# Sensors_1.net
KiCad netlist of a schematic drawn in Altium Designer
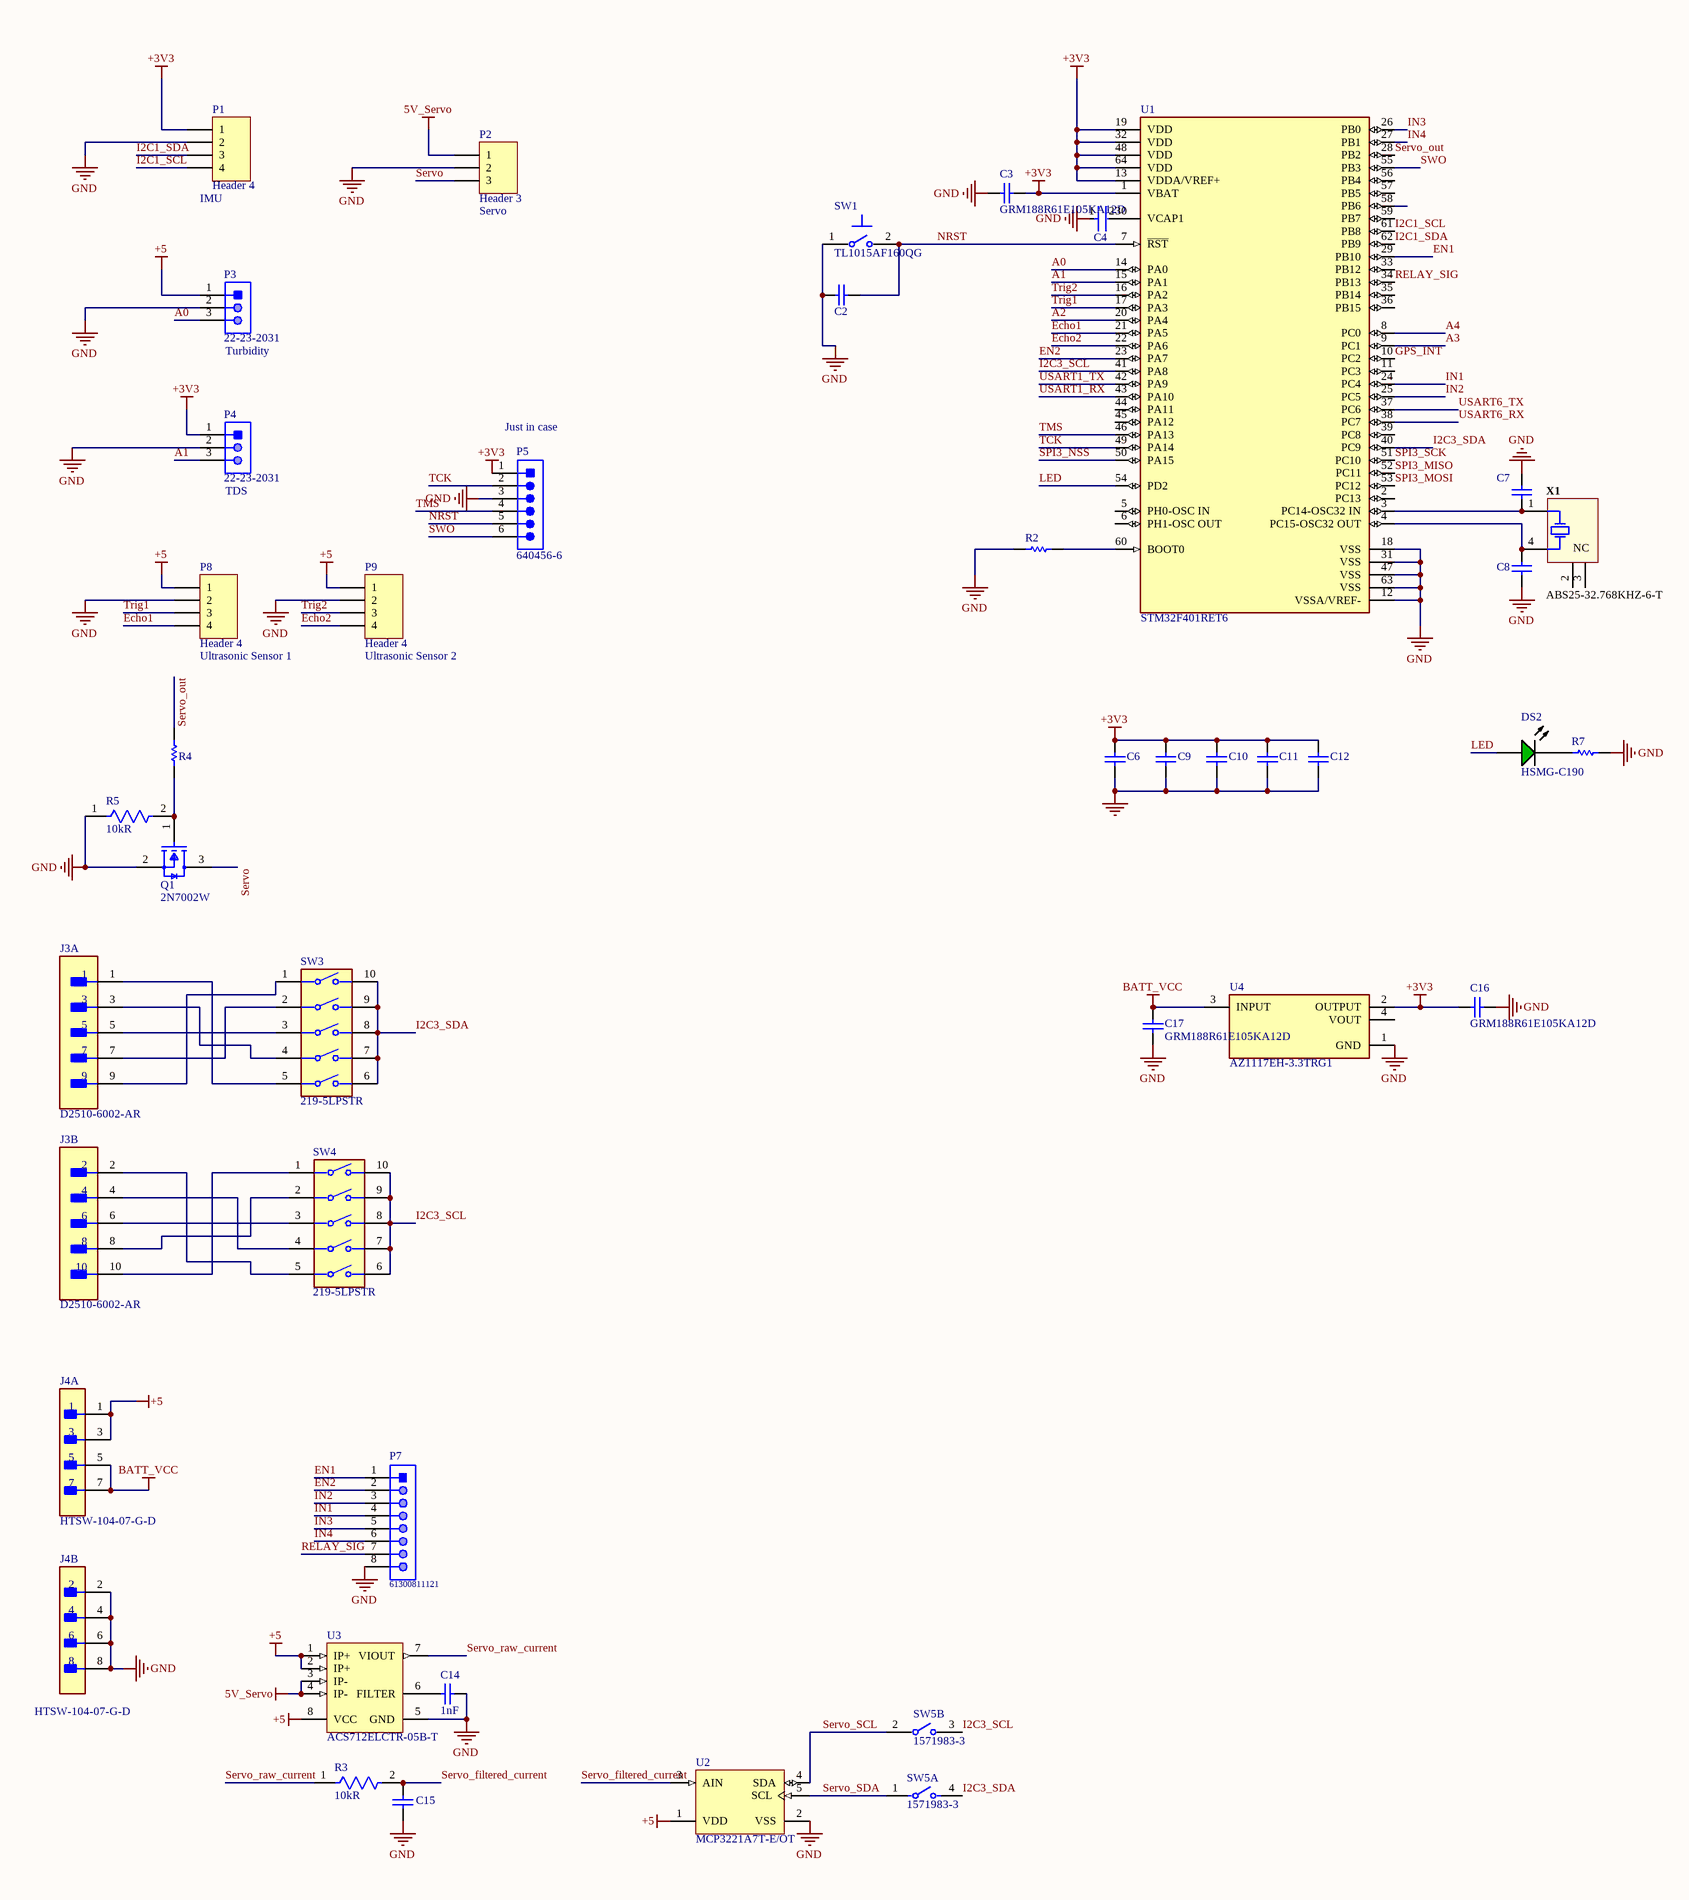
[diagram p0: Sensors_1.SchDoc, left]
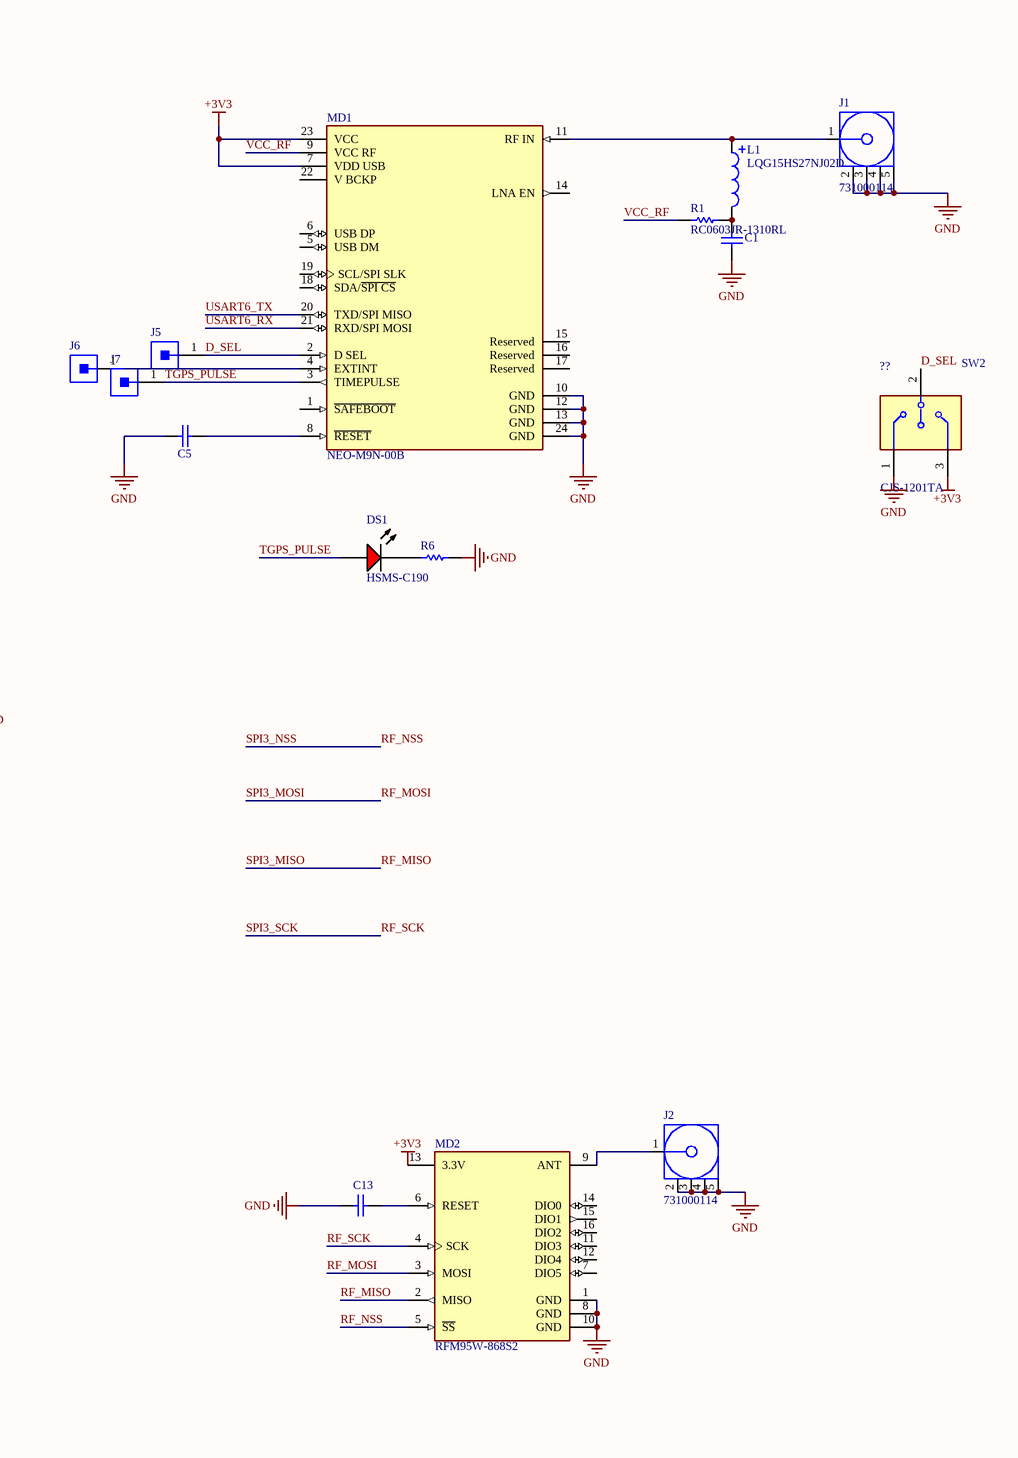
[diagram p1: Sensors_1.SchDoc, right]

(export (version "E")
  (design (tool "Eeschema 10.0.6"))
  (components
    (comp (ref "C1")
      (value "0603YC104KAT2A")
      (footprint "CAPC1608X90X35NL15T15")
      (description "Chip Capacitor, 100 nF, +/- 10%, 16 V, -55 to 125 degC, 0603 (1608 Metric), RoHS, Tape and Reel")
      (fields (field (name "MANUFACTURER") "AVX"))
      (libsource (lib "Altium Content Vault") (part "CAP-NP-2"))
    )
    (comp (ref "C2")
      (value "0603YC104KAZ2A")
      (footprint "CAPC1608X90X35ML15T15")
      (fields (field (name "MANUFACTURER") "AVX Interconnect / Elco"))
      (libsource (lib "Altium Content Vault") (part "CAP"))
    )
    (comp (ref "C3")
      (value "GRM188R61E105KA12D")
      (footprint "CAPC1608X90X35NL10T15")
      (fields (field (name "MANUFACTURER") "Murata"))
      (libsource (lib "Altium Content Vault") (part "CAP"))
    )
    (comp (ref "C4")
      (value "CL10X475KQ8NNNC")
      (footprint "FP-CL10-IPC_A")
      (description "Cap Ceramic 4.7uF 6.3V X6S ±10% Pad SMD 0603 +105°C T/R")
      (fields (field (name "TOLERANCE") "10%"))
      (libsource (lib "Altium Content Vault") (part "b4654b650e69147ec39a6b967a45e02"))
    )
    (comp (ref "C5")
      (value "0603YC104KAZ2A")
      (footprint "CAPC1608X90X35ML15T15")
      (fields (field (name "MANUFACTURER") "AVX Interconnect / Elco"))
      (libsource (lib "Altium Content Vault") (part "CAP"))
    )
    (comp (ref "C6")
      (value "0603YC104KAZ2A")
      (footprint "CAPC1608X90X35ML15T15")
      (fields (field (name "MANUFACTURER") "AVX Interconnect / Elco"))
      (libsource (lib "Altium Content Vault") (part "CAP"))
    )
    (comp (ref "C7")
      (value "GQM1885C2A4R3BB01D")
      (footprint "CAPC1608X90X35LL10T15")
      (fields (field (name "MANUFACTURER") "Murata"))
      (libsource (lib "Altium Content Vault") (part "CAP"))
    )
    (comp (ref "C8")
      (value "GQM1885C2A4R3BB01D")
      (footprint "CAPC1608X90X35LL10T15")
      (fields (field (name "MANUFACTURER") "Murata"))
      (libsource (lib "Altium Content Vault") (part "CAP"))
    )
    (comp (ref "C9")
      (value "0603YC104KAZ2A")
      (footprint "CAPC1608X90X35ML15T15")
      (fields (field (name "MANUFACTURER") "AVX Interconnect / Elco"))
      (libsource (lib "Altium Content Vault") (part "CAP"))
    )
    (comp (ref "C10")
      (value "0603YC104KAZ2A")
      (footprint "CAPC1608X90X35ML15T15")
      (fields (field (name "MANUFACTURER") "AVX Interconnect / Elco"))
      (libsource (lib "Altium Content Vault") (part "CAP"))
    )
    (comp (ref "C11")
      (value "0603YC104KAZ2A")
      (footprint "CAPC1608X90X35ML15T15")
      (fields (field (name "MANUFACTURER") "AVX Interconnect / Elco"))
      (libsource (lib "Altium Content Vault") (part "CAP"))
    )
    (comp (ref "C12")
      (value "0603YC104KAZ2A")
      (footprint "CAPC1608X90X35ML15T15")
      (fields (field (name "MANUFACTURER") "AVX Interconnect / Elco"))
      (libsource (lib "Altium Content Vault") (part "CAP"))
    )
    (comp (ref "C13")
      (value "0603YC104KAZ2A")
      (footprint "CAPC1608X90X35ML15T15")
      (fields (field (name "MANUFACTURER") "AVX Interconnect / Elco"))
      (libsource (lib "Altium Content Vault") (part "CAP"))
    )
    (comp (ref "C14")
      (value "1nF")
      (footprint "CAPC1608X95X40LL15T15")
      (fields (field (name "PART NUMBER") "VJ0603Y102KXACW1BC") (field (name "MANUFACTURER") "Vitramon"))
      (libsource (lib "Altium Content Vault") (part "CAP"))
    )
    (comp (ref "C15")
      (value "GRM188R60J106ME47D")
      (footprint "CAPC1608X90X35NL10T15")
      (fields (field (name "MANUFACTURER") "Murata"))
      (libsource (lib "Altium Content Vault") (part "CAP"))
    )
    (comp (ref "C16")
      (value "GRM188R61E105KA12D")
      (footprint "CAPC1608X90X35NL10T15")
      (fields (field (name "MANUFACTURER") "Murata"))
      (libsource (lib "Altium Content Vault") (part "CAP"))
    )
    (comp (ref "C17")
      (value "GRM188R61E105KA12D")
      (footprint "CAPC1608X90X35NL10T15")
      (fields (field (name "MANUFACTURER") "Murata"))
      (libsource (lib "Altium Content Vault") (part "CAP"))
    )
    (comp (ref "DS1")
      (value "HSMS-C190")
      (footprint "AVAG-HSMX-C190_V")
      (description "LED Uni-Color Red, 52 mW, 20 mA, -40 to 85 degC, 2-Pin SMD, RoHS, Tape and Reel")
      (fields (field (name "MANUFACTURER") "Avago"))
      (libsource (lib "Altium Content Vault") (part "LED-RED-AK-2"))
    )
    (comp (ref "DS2")
      (value "HSMG-C190")
      (footprint "AVAG-HSMX-C190_V")
      (description "Chip LED, Green, 2.2 V, -40 to 85 degC, 2-Pin SMD, RoHS, Tape and Reel")
      (libsource (lib "Altium Content Vault") (part "LED-GREEN-AK-2"))
    )
    (comp (ref "J1")
      (value "731000114")
      (footprint "MOLX-731000114_V")
      (description "SMA Right-Angle PCB Jack Receptacle, Brass Body, Gold Plated, 50 Ohm, 5-Pin THD, RoHS, Tray")
      (fields (field (name "MANUFACTURER") "Molex"))
      (libsource (lib "Altium Content Vault") (part "CN-S-4F-RF5"))
    )
    (comp (ref "J2")
      (value "731000114")
      (footprint "MOLX-731000114_V")
      (description "SMA Right-Angle PCB Jack Receptacle, Brass Body, Gold Plated, 50 Ohm, 5-Pin THD, RoHS, Tray")
      (fields (field (name "MANUFACTURER") "Molex"))
      (libsource (lib "Altium Content Vault") (part "CN-S-4F-RF5"))
    )
    (comp (ref "J3")
      (value "D2510-6002-AR")
      (footprint "FP-D2510-6002-AR-MFG")
      (description "CONN HEADER VERT 10POS 2.54MM")
      (fields
        (field (name "MANUFACTURER") "3M")
        (field (name "OCTOPART") "https://octopart.com/d2510-6002-ar-3m-8399032")
      )
      (libsource (lib "Altium Content Vault") (part "e3d72e3fae012c5d23a5abbd4905472"))
    )
    (comp (ref "J4")
      (value "HTSW-104-07-G-D")
      (footprint "FP-HTSW-104-07-G-D-MFG")
      (description "CONN HEADER VERT 8POS 2.54MM")
      (fields
        (field (name "MANUFACTURER") "Samtec")
        (field (name "OCTOPART") "https://octopart.com/htsw-104-07-g-d-samtec-10613822")
      )
      (libsource (lib "Altium Content Vault") (part "811e954b9c034aa737de4d9295cbe7e"))
    )
    (comp (ref "J5")
      (value "61300111121")
      (footprint "61300111121")
      (description "THT Vertical Pin Header WR-PHD, Pitch 2.54 mm, Single Row, 1 pins")
      (fields (field (name "MANUFACTURER") "Wurth Elektronik") (field (name "PUBLISHER") "WurthElektronik"))
      (libsource (lib "Altium Content Vault") (part "WE-CN-1P-M-R1"))
    )
    (comp (ref "J6")
      (value "61300111121")
      (footprint "61300111121")
      (description "THT Vertical Pin Header WR-PHD, Pitch 2.54 mm, Single Row, 1 pins")
      (fields (field (name "MANUFACTURER") "Wurth Elektronik") (field (name "PUBLISHER") "WurthElektronik"))
      (libsource (lib "Altium Content Vault") (part "WE-CN-1P-M-R1"))
    )
    (comp (ref "J7")
      (value "61300111121")
      (footprint "61300111121")
      (description "THT Vertical Pin Header WR-PHD, Pitch 2.54 mm, Single Row, 1 pins")
      (fields (field (name "MANUFACTURER") "Wurth Elektronik") (field (name "PUBLISHER") "WurthElektronik"))
      (libsource (lib "Altium Content Vault") (part "WE-CN-1P-M-R1"))
    )
    (comp (ref "L1")
      (value "LQG15HS27NJ02D")
      (footprint "IND1005X55X25LL5T10")
      (description "Chip Inductor, 27 nH, 5%, 300 mA, -55 to 125 degC, 2-Pin SMD (0402), RoHS, Tape and Reel")
      (fields (field (name "TOLERANCE") "±5%") (field (name "MANUFACTURER") "Murata"))
      (libsource (lib "Altium Content Vault") (part "IND_POLAR-2"))
    )
    (comp (ref "MD1")
      (value "NEO-M9N-00B")
      (footprint "FP-NEO-M9N-00B-MFG")
      (description "M9 standard precision module")
      (fields
        (field (name "MANUFACTURER") "u-blox")
        (field (name "OCTOPART") "https://octopart.com/neo-m9n-00b-u-blox-107315722")
      )
      (libsource (lib "Altium Content Vault") (part "237a2c67e0e2927394476258baea46c"))
    )
    (comp (ref "MD2")
      (value "RFM95W-868S2")
      (footprint "FP-RFM95W-868S2-MFG")
      (description "RX TXRX MODULE ISM < 1GHZ SMD")
      (libsource (lib "Altium Content Vault") (part "17626aa6fba47fab2b206b7c140802e"))
    )
    (comp (ref "P1")
      (value "Header 4")
      (footprint "HDR1X4")
      (description "Header, 4-Pin")
      (fields (field (name "PUBLISHER") "Altium Limited"))
      (libsource (lib "Miscellaneous Connectors") (part "Header 4"))
    )
    (comp (ref "P2")
      (value "Header 3")
      (footprint "HDR1X3")
      (description "Header, 3-Pin")
      (fields (field (name "PUBLISHER") "Altium Limited"))
      (libsource (lib "Miscellaneous Connectors") (part "Header 3"))
    )
    (comp (ref "P3")
      (value "22-23-2031")
      (footprint "MOLX-22-23-2031_V")
      (description "Male Header, Pitch 2.54 mm, 1 x 3 Position, Height 8.18 mm, Tail Length 3.56 mm, RoHS, Bulk")
      (fields (field (name "MANUFACTURER") "Molex"))
      (libsource (lib "Altium Content Vault") (part "CN-1P-M-R3"))
    )
    (comp (ref "P4")
      (value "22-23-2031")
      (footprint "MOLX-22-23-2031_V")
      (description "Male Header, Pitch 2.54 mm, 1 x 3 Position, Height 8.18 mm, Tail Length 3.56 mm, RoHS, Bulk")
      (fields (field (name "MANUFACTURER") "Molex"))
      (libsource (lib "Altium Content Vault") (part "CN-1P-M-R3"))
    )
    (comp (ref "P5")
      (value "640456-6")
      (footprint "TECO-640456-6_V")
      (fields (field (name "MANUFACTURER") "TE Connectivity"))
      (libsource (lib "Altium Content Vault") (part "CN-1P-M-R6"))
    )
    (comp (ref "P7")
      (value "61300811121")
      (footprint "61300811121")
      (description "THT Vertical Pin Header WR-PHD, Pitch 2.54 mm, Single Row, 8 pins")
      (fields (field (name "MANUFACTURER") "Wurth Elektronik") (field (name "PUBLISHER") "WurthElektronik"))
      (libsource (lib "Altium Content Vault") (part "WE-CN-1P-M-R8"))
    )
    (comp (ref "P8")
      (value "Header 4")
      (footprint "HDR1X4")
      (description "Header, 4-Pin")
      (fields (field (name "PUBLISHER") "Altium Limited"))
      (libsource (lib "Miscellaneous Connectors") (part "Header 4"))
    )
    (comp (ref "P9")
      (value "Header 4")
      (footprint "HDR1X4")
      (description "Header, 4-Pin")
      (fields (field (name "PUBLISHER") "Altium Limited"))
      (libsource (lib "Miscellaneous Connectors") (part "Header 4"))
    )
    (comp (ref "Q1")
      (value "2N7002W")
      (footprint "FP-419AB-01-IPC_C")
      (description "MOSFET N-CH 60V 115MA SOT-323")
      (libsource (lib "Altium Content Vault") (part "a04dfd38ebfed9f67ad7f4c51a87371"))
    )
    (comp (ref "R1")
      (value "RC0603JR-1310RL")
      (footprint "RESC1608X55X25LL10T15")
      (fields (field (name "MANUFACTURER") "Yageo"))
      (libsource (lib "Altium Content Vault") (part "RES"))
    )
    (comp (ref "R2")
      (value "CRCW060310K0FKEA")
      (footprint "RESC1609X50X30NL8T20")
      (description "Chip Resistor, 10 KOhm, +/- 1%, 100 mW, -55 to 155 degC, 0603 (1608 Metric), RoHS, Tape and Reel")
      (fields (field (name "MANUFACTURER") "Vishay Semiconductor"))
      (libsource (lib "Altium Content Vault") (part "RES-2"))
    )
    (comp (ref "R3")
      (value "MCT0603MD1002BP100")
      (footprint "FP-MCT0603-IPC_B")
      (description "RES SMD 100 OHM 1% 1/8W 0603")
      (fields (field (name "RESISTANCE") "10kR") (field (name "TOLERANCE") "0.1%"))
      (libsource (lib "Altium Content Vault") (part "1029c3af85768c4190bb7ad29bc67b5"))
    )
    (comp (ref "R4")
      (value "RC0603FR-101KL")
      (footprint "RESC1608X55X25LL10T15")
      (fields (field (name "MANUFACTURER") "Yageo"))
      (libsource (lib "Altium Content Vault") (part "RES"))
    )
    (comp (ref "R5")
      (value "MCT0603MD1002BP100")
      (footprint "FP-MCT0603-IPC_B")
      (description "RES SMD 100 OHM 1% 1/8W 0603")
      (fields (field (name "RESISTANCE") "10kR") (field (name "TOLERANCE") "0.1%"))
      (libsource (lib "Altium Content Vault") (part "1029c3af85768c4190bb7ad29bc67b5"))
    )
    (comp (ref "R6")
      (value "ERJ3EKF3300V")
      (footprint "RESC1608X55X30ML15T15")
      (fields (field (name "MANUFACTURER") "Panasonic"))
      (libsource (lib "Altium Content Vault") (part "RES"))
    )
    (comp (ref "R7")
      (value "ERJ3EKF3300V")
      (footprint "RESC1608X55X30ML15T15")
      (fields (field (name "MANUFACTURER") "Panasonic"))
      (libsource (lib "Altium Content Vault") (part "RES"))
    )
    (comp (ref "SW1")
      (value "TL1015AF160QG")
      (footprint "FP-TL1015AF160QG-MFG")
      (description "SWITCH TACTILE SPST-NO 0.05A 12V")
      (libsource (lib "Altium Content Vault") (part "2041f8efb62e6aaa548c9fd35e2c2f1"))
    )
    (comp (ref "SW2")
      (value "CJS-1201TA")
      (footprint "FP-CJS-1201TA-MFG")
      (description "SWITCH SLIDE SPDT 100MA 6V")
      (fields
        (field (name "OCTOPART") "https://octopart.com/cjs-1201ta-nidec+copal-87363567")
        (field (name "MANUFACTURER") "Copal Electronics Inc")
      )
      (libsource (lib "Altium Content Vault") (part "c06ada37f0df4dbec3756164f145c54"))
    )
    (comp (ref "SW3")
      (value "219-5LPSTR")
      (footprint "FP-219-5LPSTR-MFG")
      (description "SWITCH SLIDE DIP SPST 100MA 20V")
      (libsource (lib "Altium Content Vault") (part "5dac19a08bf10035f124d79214233cd"))
    )
    (comp (ref "SW4")
      (value "219-5LPSTR")
      (footprint "FP-219-5LPSTR-MFG")
      (description "SWITCH SLIDE DIP SPST 100MA 20V")
      (libsource (lib "Altium Content Vault") (part "5dac19a08bf10035f124d79214233cd"))
    )
    (comp (ref "SW5")
      (value "1571983-3")
      (footprint "FP-1571983-3-MFG")
      (description "SWITCH SLIDE DIP SPST 25MA 24V")
      (fields
        (field (name "OCTOPART") "https://octopart.com/1571983-3-te+connectivity-46507520")
        (field (name "MANUFACTURER") "TE Connectivity")
      )
      (libsource (lib "Altium Content Vault") (part "305b8df74c9585226458c49fb7f7021"))
    )
    (comp (ref "U1")
      (value "STM32F401RET6")
      (footprint "FP-LQFP64-5W-MFG")
      (description "IC MCU 32BIT 512KB FLASH 64LQFP")
      (fields
        (field (name "OCTOPART") "https://octopart.com/stm32f401ret6-stmicroelectronics-34185993")
        (field (name "MANUFACTURER") "STMicroelectronics")
      )
      (libsource (lib "Altium Content Vault") (part "7f49e7cdc56bbeda8d86db7d775c506"))
    )
    (comp (ref "U2")
      (value "MCP3221A7T-E/OT")
      (footprint "SOT-23-OT5_N")
      (libsource (lib "Altium Content Vault") (part "CON-ADC-MCP3021-5"))
    )
    (comp (ref "U3")
      (value "ACS712ELCTR-05B-T")
      (footprint "ALEG-LC-8_V")
      (fields (field (name "MANUFACTURER") "Allegro Microsystems"))
      (libsource (lib "Altium Content Vault") (part "ALEG-ACS712-SOIC-8"))
    )
    (comp (ref "U4")
      (value "AZ1117EH-3.3TRG1")
      (footprint "FP-SOT223-MFG")
      (description "IC REG LINEAR 3.3V 1A SOT223")
      (libsource (lib "Altium Content Vault") (part "d973f545ad55d44feb2bbb755596838"))
    )
    (comp (ref "X1")
      (value "ABS25-32.768KHZ-6-T")
      (footprint "ABRA-ABS25-4_V")
      (fields (field (name "TOLERANCE") "20PPM") (field (name "MANUFACTURER") "Abracon"))
      (libsource (lib "Altium Content Vault") (part "ABRA-XTAL_1-4-4"))
    )
  )
  (nets
    (net (code "1") (name "+3V3") (class "Default")
      (node (ref "C10") (pin "2") (pinfunction "2_2") (pintype "passive"))
      (node (ref "C11") (pin "2") (pinfunction "2_2") (pintype "passive"))
      (node (ref "C12") (pin "2") (pinfunction "2_2") (pintype "passive"))
      (node (ref "C16") (pin "2") (pinfunction "2_2") (pintype "passive"))
      (node (ref "C3") (pin "2") (pinfunction "2_2") (pintype "passive"))
      (node (ref "C6") (pin "2") (pinfunction "2_2") (pintype "passive"))
      (node (ref "C9") (pin "2") (pinfunction "2_2") (pintype "passive"))
      (node (ref "MD1") (pin "23") (pinfunction "VCC_23") (pintype "power_in"))
      (node (ref "MD1") (pin "7") (pinfunction "VDD_USB_7") (pintype "power_in"))
      (node (ref "MD2") (pin "13") (pinfunction "3.3V_13") (pintype "power_in"))
      (node (ref "P1") (pin "1") (pinfunction "1_1") (pintype "passive"))
      (node (ref "P4") (pin "1") (pinfunction "1_1") (pintype "passive"))
      (node (ref "P5") (pin "1") (pinfunction "1_1") (pintype "passive"))
      (node (ref "SW2") (pin "3") (pinfunction "3_3") (pintype "passive"))
      (node (ref "U1") (pin "1") (pinfunction "VBAT_1") (pintype "power_in"))
      (node (ref "U1") (pin "13") (pinfunction "VDDA/VREF+_13") (pintype "power_in"))
      (node (ref "U1") (pin "19") (pinfunction "VDD_19") (pintype "power_in"))
      (node (ref "U1") (pin "32") (pinfunction "VDD_32") (pintype "power_in"))
      (node (ref "U1") (pin "48") (pinfunction "VDD_48") (pintype "power_in"))
      (node (ref "U1") (pin "64") (pinfunction "VDD_64") (pintype "power_in"))
      (node (ref "U4") (pin "2") (pinfunction "OUTPUT_2") (pintype "power_in"))
    )
    (net (code "2") (name "+5") (class "Default")
      (node (ref "J4") (pin "1") (pinfunction "1_1") (pintype "passive"))
      (node (ref "J4") (pin "3") (pinfunction "3_3") (pintype "passive"))
      (node (ref "P3") (pin "1") (pinfunction "1_1") (pintype "passive"))
      (node (ref "P8") (pin "1") (pinfunction "1_1") (pintype "passive"))
      (node (ref "P9") (pin "1") (pinfunction "1_1") (pintype "passive"))
      (node (ref "U2") (pin "1") (pinfunction "VDD_1") (pintype "power_in"))
      (node (ref "U3") (pin "1") (pinfunction "IP+_1") (pintype "input"))
      (node (ref "U3") (pin "2") (pinfunction "IP+_2") (pintype "input"))
      (node (ref "U3") (pin "8") (pinfunction "VCC_8") (pintype "power_in"))
    )
    (net (code "3") (name "/A0") (class "Default")
      (node (ref "P3") (pin "3") (pinfunction "3_3") (pintype "passive"))
      (node (ref "U1") (pin "14") (pinfunction "PA0_14") (pintype "bidirectional"))
    )
    (net (code "4") (name "/A1") (class "Default")
      (node (ref "P4") (pin "3") (pinfunction "3_3") (pintype "passive"))
      (node (ref "U1") (pin "15") (pinfunction "PA1_15") (pintype "bidirectional"))
    )
    (net (code "5") (name "/A2") (class "Default")
      (node (ref "U1") (pin "20") (pinfunction "PA4_20") (pintype "bidirectional"))
    )
    (net (code "6") (name "/A3") (class "Default")
      (node (ref "U1") (pin "9") (pinfunction "PC1_9") (pintype "bidirectional"))
    )
    (net (code "7") (name "/A4") (class "Default")
      (node (ref "U1") (pin "8") (pinfunction "PC0_8") (pintype "bidirectional"))
    )
    (net (code "8") (name "/D_SEL") (class "Default")
      (node (ref "J5") (pin "1") (pinfunction "1_1") (pintype "passive"))
      (node (ref "MD1") (pin "2") (pinfunction "D_SEL_2") (pintype "input"))
      (node (ref "SW2") (pin "2") (pinfunction "C_2") (pintype "passive"))
    )
    (net (code "9") (name "/EN1") (class "Default")
      (node (ref "P7") (pin "1") (pinfunction "1_1") (pintype "passive"))
      (node (ref "U1") (pin "29") (pinfunction "PB10_29") (pintype "bidirectional"))
    )
    (net (code "10") (name "/EN2") (class "Default")
      (node (ref "P7") (pin "2") (pinfunction "2_2") (pintype "passive"))
      (node (ref "U1") (pin "23") (pinfunction "PA7_23") (pintype "bidirectional"))
    )
    (net (code "11") (name "/Echo1") (class "Default")
      (node (ref "P8") (pin "4") (pinfunction "4_4") (pintype "passive"))
      (node (ref "U1") (pin "21") (pinfunction "PA5_21") (pintype "bidirectional"))
    )
    (net (code "12") (name "/Echo2") (class "Default")
      (node (ref "P9") (pin "4") (pinfunction "4_4") (pintype "passive"))
      (node (ref "U1") (pin "22") (pinfunction "PA6_22") (pintype "bidirectional"))
    )
    (net (code "13") (name "/GPS_INT") (class "Default")
      (node (ref "U1") (pin "10") (pinfunction "PC2_10") (pintype "bidirectional"))
    )
    (net (code "14") (name "/I2C1_SCL") (class "Default")
      (node (ref "P1") (pin "4") (pinfunction "4_4") (pintype "passive"))
      (node (ref "U1") (pin "61") (pinfunction "PB8_61") (pintype "bidirectional"))
    )
    (net (code "15") (name "/I2C1_SDA") (class "Default")
      (node (ref "P1") (pin "3") (pinfunction "3_3") (pintype "passive"))
      (node (ref "U1") (pin "62") (pinfunction "PB9_62") (pintype "bidirectional"))
    )
    (net (code "16") (name "/I2C3_SCL") (class "Default")
      (node (ref "SW4") (pin "10") (pinfunction "10_10") (pintype "passive"))
      (node (ref "SW4") (pin "6") (pinfunction "6_6") (pintype "passive"))
      (node (ref "SW4") (pin "7") (pinfunction "7_7") (pintype "passive"))
      (node (ref "SW4") (pin "8") (pinfunction "8_8") (pintype "passive"))
      (node (ref "SW4") (pin "9") (pinfunction "9_9") (pintype "passive"))
      (node (ref "SW5") (pin "3") (pinfunction "3_3") (pintype "passive"))
      (node (ref "U1") (pin "41") (pinfunction "PA8_41") (pintype "bidirectional"))
    )
    (net (code "17") (name "/I2C3_SDA") (class "Default")
      (node (ref "SW3") (pin "10") (pinfunction "10_10") (pintype "passive"))
      (node (ref "SW3") (pin "6") (pinfunction "6_6") (pintype "passive"))
      (node (ref "SW3") (pin "7") (pinfunction "7_7") (pintype "passive"))
      (node (ref "SW3") (pin "8") (pinfunction "8_8") (pintype "passive"))
      (node (ref "SW3") (pin "9") (pinfunction "9_9") (pintype "passive"))
      (node (ref "SW5") (pin "4") (pinfunction "4_4") (pintype "passive"))
      (node (ref "U1") (pin "40") (pinfunction "PC9_40") (pintype "bidirectional"))
    )
    (net (code "18") (name "/IN1") (class "Default")
      (node (ref "P7") (pin "4") (pinfunction "4_4") (pintype "passive"))
      (node (ref "U1") (pin "24") (pinfunction "PC4_24") (pintype "bidirectional"))
    )
    (net (code "19") (name "/IN2") (class "Default")
      (node (ref "P7") (pin "3") (pinfunction "3_3") (pintype "passive"))
      (node (ref "U1") (pin "25") (pinfunction "PC5_25") (pintype "bidirectional"))
    )
    (net (code "20") (name "/IN3") (class "Default")
      (node (ref "P7") (pin "5") (pinfunction "5_5") (pintype "passive"))
      (node (ref "U1") (pin "26") (pinfunction "PB0_26") (pintype "bidirectional"))
    )
    (net (code "21") (name "/IN4") (class "Default")
      (node (ref "P7") (pin "6") (pinfunction "6_6") (pintype "passive"))
      (node (ref "U1") (pin "27") (pinfunction "PB1_27") (pintype "bidirectional"))
    )
    (net (code "22") (name "/LED") (class "Default")
      (node (ref "DS2") (pin "1") (pinfunction "A_1") (pintype "passive"))
      (node (ref "U1") (pin "54") (pinfunction "PD2_54") (pintype "bidirectional"))
    )
    (net (code "23") (name "/NRST") (class "Default")
      (node (ref "C2") (pin "1") (pinfunction "1_1") (pintype "passive"))
      (node (ref "P5") (pin "5") (pinfunction "5_5") (pintype "passive"))
      (node (ref "SW1") (pin "2") (pinfunction "2_2") (pintype "passive"))
      (node (ref "U1") (pin "7") (pinfunction "~{RST}_7") (pintype "input"))
    )
    (net (code "24") (name "/RELAY_SIG") (class "Default")
      (node (ref "P7") (pin "7") (pinfunction "7_7") (pintype "passive"))
      (node (ref "U1") (pin "34") (pinfunction "PB13_34") (pintype "bidirectional"))
    )
    (net (code "25") (name "/RF_MISO") (class "Default")
      (node (ref "MD2") (pin "2") (pinfunction "MISO_2") (pintype "output"))
      (node (ref "U1") (pin "52") (pinfunction "PC11_52") (pintype "bidirectional"))
    )
    (net (code "26") (name "/RF_MOSI") (class "Default")
      (node (ref "MD2") (pin "3") (pinfunction "MOSI_3") (pintype "input"))
      (node (ref "U1") (pin "53") (pinfunction "PC12_53") (pintype "bidirectional"))
    )
    (net (code "27") (name "/RF_NSS") (class "Default")
      (node (ref "MD2") (pin "5") (pinfunction "~{SS}_5") (pintype "input"))
      (node (ref "U1") (pin "50") (pinfunction "PA15_50") (pintype "bidirectional"))
    )
    (net (code "28") (name "/RF_SCK") (class "Default")
      (node (ref "MD2") (pin "4") (pinfunction "SCK_4") (pintype "input"))
      (node (ref "U1") (pin "51") (pinfunction "PC10_51") (pintype "bidirectional"))
    )
    (net (code "29") (name "/SWO") (class "Default")
      (node (ref "P5") (pin "6") (pinfunction "6_6") (pintype "passive"))
      (node (ref "U1") (pin "55") (pinfunction "PB3_55") (pintype "bidirectional"))
    )
    (net (code "30") (name "/Servo") (class "Default")
      (node (ref "P2") (pin "3") (pinfunction "3_3") (pintype "passive"))
      (node (ref "Q1") (pin "3") (pinfunction "Drain_3") (pintype "passive"))
    )
    (net (code "31") (name "/Servo_SCL") (class "Default")
      (node (ref "SW5") (pin "2") (pinfunction "2_2") (pintype "passive"))
      (node (ref "U2") (pin "4") (pinfunction "SDA_4") (pintype "bidirectional"))
    )
    (net (code "32") (name "/Servo_SDA") (class "Default")
      (node (ref "SW5") (pin "1") (pinfunction "1_1") (pintype "passive"))
      (node (ref "U2") (pin "5") (pinfunction "SCL_5") (pintype "input"))
    )
    (net (code "33") (name "/Servo_filtered_current") (class "Default")
      (node (ref "C15") (pin "2") (pinfunction "2_2") (pintype "passive"))
      (node (ref "R3") (pin "2") (pinfunction "2_2") (pintype "passive"))
      (node (ref "U2") (pin "3") (pinfunction "AIN_3") (pintype "input"))
    )
    (net (code "34") (name "/Servo_out") (class "Default")
      (node (ref "R4") (pin "1") (pinfunction "1_1") (pintype "passive"))
      (node (ref "U1") (pin "28") (pinfunction "PB2_28") (pintype "bidirectional"))
    )
    (net (code "35") (name "/Servo_raw_current") (class "Default")
      (node (ref "R3") (pin "1") (pinfunction "1_1") (pintype "passive"))
      (node (ref "U3") (pin "7") (pinfunction "VIOUT_7") (pintype "output"))
    )
    (net (code "36") (name "/TCK") (class "Default")
      (node (ref "P5") (pin "2") (pinfunction "2_2") (pintype "passive"))
      (node (ref "U1") (pin "49") (pinfunction "PA14_49") (pintype "bidirectional"))
    )
    (net (code "37") (name "/TGPS_PULSE") (class "Default")
      (node (ref "DS1") (pin "1") (pinfunction "A_1") (pintype "passive"))
      (node (ref "J7") (pin "1") (pinfunction "1_1") (pintype "passive"))
      (node (ref "MD1") (pin "3") (pinfunction "TIMEPULSE_3") (pintype "output"))
    )
    (net (code "38") (name "/TMS") (class "Default")
      (node (ref "P5") (pin "4") (pinfunction "4_4") (pintype "passive"))
      (node (ref "U1") (pin "46") (pinfunction "PA13_46") (pintype "bidirectional"))
    )
    (net (code "39") (name "/Trig1") (class "Default")
      (node (ref "P8") (pin "3") (pinfunction "3_3") (pintype "passive"))
      (node (ref "U1") (pin "17") (pinfunction "PA3_17") (pintype "bidirectional"))
    )
    (net (code "40") (name "/Trig2") (class "Default")
      (node (ref "P9") (pin "3") (pinfunction "3_3") (pintype "passive"))
      (node (ref "U1") (pin "16") (pinfunction "PA2_16") (pintype "bidirectional"))
    )
    (net (code "41") (name "/USART1_RX") (class "Default")
      (node (ref "U1") (pin "43") (pinfunction "PA10_43") (pintype "bidirectional"))
    )
    (net (code "42") (name "/USART1_TX") (class "Default")
      (node (ref "U1") (pin "42") (pinfunction "PA9_42") (pintype "bidirectional"))
    )
    (net (code "43") (name "/USART6_RX") (class "Default")
      (node (ref "MD1") (pin "21") (pinfunction "RXD/SPI_MOSI_21") (pintype "bidirectional"))
      (node (ref "U1") (pin "38") (pinfunction "PC7_38") (pintype "bidirectional"))
    )
    (net (code "44") (name "/USART6_TX") (class "Default")
      (node (ref "MD1") (pin "20") (pinfunction "TXD/SPI_MISO_20") (pintype "bidirectional"))
      (node (ref "U1") (pin "37") (pinfunction "PC6_37") (pintype "bidirectional"))
    )
    (net (code "45") (name "/VCC_RF") (class "Default")
      (node (ref "MD1") (pin "9") (pinfunction "VCC_RF_9") (pintype "power_in"))
      (node (ref "R1") (pin "1") (pinfunction "1_1") (pintype "passive"))
    )
    (net (code "46") (name "5V_Servo") (class "Default")
      (node (ref "P2") (pin "1") (pinfunction "1_1") (pintype "passive"))
      (node (ref "U3") (pin "3") (pinfunction "IP-_3") (pintype "input"))
      (node (ref "U3") (pin "4") (pinfunction "IP-_4") (pintype "input"))
    )
    (net (code "47") (name "BATT_VCC") (class "Default")
      (node (ref "C17") (pin "2") (pinfunction "2_2") (pintype "passive"))
      (node (ref "J4") (pin "5") (pinfunction "5_5") (pintype "passive"))
      (node (ref "J4") (pin "7") (pinfunction "7_7") (pintype "passive"))
      (node (ref "U4") (pin "3") (pinfunction "INPUT_3") (pintype "power_in"))
    )
    (net (code "48") (name "GND") (class "Default")
      (node (ref "C1") (pin "2") (pinfunction "2_2") (pintype "passive"))
      (node (ref "C10") (pin "1") (pinfunction "1_1") (pintype "passive"))
      (node (ref "C11") (pin "1") (pinfunction "1_1") (pintype "passive"))
      (node (ref "C12") (pin "1") (pinfunction "1_1") (pintype "passive"))
      (node (ref "C13") (pin "1") (pinfunction "1_1") (pintype "passive"))
      (node (ref "C14") (pin "1") (pinfunction "1_1") (pintype "passive"))
      (node (ref "C15") (pin "1") (pinfunction "1_1") (pintype "passive"))
      (node (ref "C16") (pin "1") (pinfunction "1_1") (pintype "passive"))
      (node (ref "C17") (pin "1") (pinfunction "1_1") (pintype "passive"))
      (node (ref "C2") (pin "2") (pinfunction "2_2") (pintype "passive"))
      (node (ref "C3") (pin "1") (pinfunction "1_1") (pintype "passive"))
      (node (ref "C4") (pin "1") (pinfunction "1_1") (pintype "passive"))
      (node (ref "C5") (pin "2") (pinfunction "2_2") (pintype "passive"))
      (node (ref "C6") (pin "1") (pinfunction "1_1") (pintype "passive"))
      (node (ref "C7") (pin "2") (pinfunction "2_2") (pintype "passive"))
      (node (ref "C8") (pin "1") (pinfunction "1_1") (pintype "passive"))
      (node (ref "C9") (pin "1") (pinfunction "1_1") (pintype "passive"))
      (node (ref "J1") (pin "2") (pinfunction "2_2") (pintype "passive"))
      (node (ref "J1") (pin "3") (pinfunction "3_3") (pintype "passive"))
      (node (ref "J1") (pin "4") (pinfunction "4_4") (pintype "passive"))
      (node (ref "J1") (pin "5") (pinfunction "5_5") (pintype "passive"))
      (node (ref "J2") (pin "2") (pinfunction "2_2") (pintype "passive"))
      (node (ref "J2") (pin "3") (pinfunction "3_3") (pintype "passive"))
      (node (ref "J2") (pin "4") (pinfunction "4_4") (pintype "passive"))
      (node (ref "J2") (pin "5") (pinfunction "5_5") (pintype "passive"))
      (node (ref "J4") (pin "2") (pinfunction "2_2") (pintype "passive"))
      (node (ref "J4") (pin "4") (pinfunction "4_4") (pintype "passive"))
      (node (ref "J4") (pin "6") (pinfunction "6_6") (pintype "passive"))
      (node (ref "J4") (pin "8") (pinfunction "8_8") (pintype "passive"))
      (node (ref "MD1") (pin "10") (pinfunction "GND_10") (pintype "power_in"))
      (node (ref "MD1") (pin "12") (pinfunction "GND_12") (pintype "power_in"))
      (node (ref "MD1") (pin "13") (pinfunction "GND_13") (pintype "power_in"))
      (node (ref "MD1") (pin "24") (pinfunction "GND_24") (pintype "power_in"))
      (node (ref "MD2") (pin "1") (pinfunction "GND_1") (pintype "power_in"))
      (node (ref "MD2") (pin "10") (pinfunction "GND_10") (pintype "power_in"))
      (node (ref "MD2") (pin "8") (pinfunction "GND_8") (pintype "power_in"))
      (node (ref "P1") (pin "2") (pinfunction "2_2") (pintype "passive"))
      (node (ref "P2") (pin "2") (pinfunction "2_2") (pintype "passive"))
      (node (ref "P3") (pin "2") (pinfunction "2_2") (pintype "passive"))
      (node (ref "P4") (pin "2") (pinfunction "2_2") (pintype "passive"))
      (node (ref "P5") (pin "3") (pinfunction "3_3") (pintype "passive"))
      (node (ref "P7") (pin "8") (pinfunction "8_8") (pintype "passive"))
      (node (ref "P8") (pin "2") (pinfunction "2_2") (pintype "passive"))
      (node (ref "P9") (pin "2") (pinfunction "2_2") (pintype "passive"))
      (node (ref "Q1") (pin "2") (pinfunction "Source_2") (pintype "passive"))
      (node (ref "R2") (pin "1") (pinfunction "1_1") (pintype "passive"))
      (node (ref "R5") (pin "1") (pinfunction "1_1") (pintype "passive"))
      (node (ref "R6") (pin "2") (pinfunction "2_2") (pintype "passive"))
      (node (ref "R7") (pin "2") (pinfunction "2_2") (pintype "passive"))
      (node (ref "SW1") (pin "1") (pinfunction "1_1") (pintype "passive"))
      (node (ref "SW2") (pin "1") (pinfunction "1_1") (pintype "passive"))
      (node (ref "U1") (pin "12") (pinfunction "VSSA/VREF-_12") (pintype "power_in"))
      (node (ref "U1") (pin "18") (pinfunction "VSS_18") (pintype "power_in"))
      (node (ref "U1") (pin "31") (pinfunction "VSS_31") (pintype "power_in"))
      (node (ref "U1") (pin "47") (pinfunction "VSS_47") (pintype "power_in"))
      (node (ref "U1") (pin "63") (pinfunction "VSS_63") (pintype "power_in"))
      (node (ref "U2") (pin "2") (pinfunction "VSS_2") (pintype "power_in"))
      (node (ref "U3") (pin "5") (pinfunction "GND_5") (pintype "power_in"))
      (node (ref "U4") (pin "1") (pinfunction "GND_1") (pintype "power_in"))
    )
    (net (code "49") (name "Net-(C1-Pad1)") (class "Default")
      (node (ref "C1") (pin "1") (pinfunction "1_1") (pintype "passive"))
      (node (ref "L1") (pin "2") (pinfunction "2_2") (pintype "passive"))
      (node (ref "R1") (pin "2") (pinfunction "2_2") (pintype "passive"))
    )
    (net (code "50") (name "Net-(DS1-K)") (class "Default")
      (node (ref "DS1") (pin "2") (pinfunction "K_2") (pintype "passive"))
      (node (ref "R6") (pin "1") (pinfunction "1_1") (pintype "passive"))
    )
    (net (code "51") (name "Net-(DS2-K)") (class "Default")
      (node (ref "DS2") (pin "2") (pinfunction "K_2") (pintype "passive"))
      (node (ref "R7") (pin "1") (pinfunction "1_1") (pintype "passive"))
    )
    (net (code "52") (name "Net-(J3-Pad1)") (class "Default")
      (node (ref "J3") (pin "1") (pinfunction "1_1") (pintype "passive"))
      (node (ref "SW3") (pin "5") (pinfunction "5_5") (pintype "passive"))
    )
    (net (code "53") (name "Net-(J3-Pad2)") (class "Default")
      (node (ref "J3") (pin "2") (pinfunction "2_2") (pintype "passive"))
      (node (ref "SW4") (pin "5") (pinfunction "5_5") (pintype "passive"))
    )
    (net (code "54") (name "Net-(J3-Pad3)") (class "Default")
      (node (ref "J3") (pin "3") (pinfunction "3_3") (pintype "passive"))
      (node (ref "SW3") (pin "4") (pinfunction "4_4") (pintype "passive"))
    )
    (net (code "55") (name "Net-(J3-Pad4)") (class "Default")
      (node (ref "J3") (pin "4") (pinfunction "4_4") (pintype "passive"))
      (node (ref "SW4") (pin "4") (pinfunction "4_4") (pintype "passive"))
    )
    (net (code "56") (name "Net-(J3-Pad5)") (class "Default")
      (node (ref "J3") (pin "5") (pinfunction "5_5") (pintype "passive"))
      (node (ref "SW3") (pin "3") (pinfunction "3_3") (pintype "passive"))
    )
    (net (code "57") (name "Net-(J3-Pad6)") (class "Default")
      (node (ref "J3") (pin "6") (pinfunction "6_6") (pintype "passive"))
      (node (ref "SW4") (pin "3") (pinfunction "3_3") (pintype "passive"))
    )
    (net (code "58") (name "Net-(J3-Pad7)") (class "Default")
      (node (ref "J3") (pin "7") (pinfunction "7_7") (pintype "passive"))
      (node (ref "SW3") (pin "2") (pinfunction "2_2") (pintype "passive"))
    )
    (net (code "59") (name "Net-(J3-Pad8)") (class "Default")
      (node (ref "J3") (pin "8") (pinfunction "8_8") (pintype "passive"))
      (node (ref "SW4") (pin "2") (pinfunction "2_2") (pintype "passive"))
    )
    (net (code "60") (name "Net-(J3-Pad9)") (class "Default")
      (node (ref "J3") (pin "9") (pinfunction "9_9") (pintype "passive"))
      (node (ref "SW3") (pin "1") (pinfunction "1_1") (pintype "passive"))
    )
    (net (code "61") (name "Net-(J3-Pad10)") (class "Default")
      (node (ref "J3") (pin "10") (pinfunction "10_10") (pintype "passive"))
      (node (ref "SW4") (pin "1") (pinfunction "1_1") (pintype "passive"))
    )
    (net (code "62") (name "Net-(MD1-EXTINT)") (class "Default")
      (node (ref "J6") (pin "1") (pinfunction "1_1") (pintype "passive"))
      (node (ref "MD1") (pin "4") (pinfunction "EXTINT_4") (pintype "input"))
    )
    (net (code "63") (name "Net-(MD1-RF_IN)") (class "Default")
      (node (ref "J1") (pin "1") (pinfunction "1_1") (pintype "passive"))
      (node (ref "L1") (pin "1") (pinfunction "1_1") (pintype "passive"))
      (node (ref "MD1") (pin "11") (pinfunction "RF_IN_11") (pintype "input"))
    )
    (net (code "64") (name "Net-(MD1-~{RESET})") (class "Default")
      (node (ref "C5") (pin "1") (pinfunction "1_1") (pintype "passive"))
      (node (ref "MD1") (pin "8") (pinfunction "~{RESET}_8") (pintype "input"))
    )
    (net (code "65") (name "Net-(MD2-ANT)") (class "Default")
      (node (ref "J2") (pin "1") (pinfunction "1_1") (pintype "passive"))
      (node (ref "MD2") (pin "9") (pinfunction "ANT_9") (pintype "passive"))
    )
    (net (code "66") (name "Net-(MD2-RESET)") (class "Default")
      (node (ref "C13") (pin "2") (pinfunction "2_2") (pintype "passive"))
      (node (ref "MD2") (pin "6") (pinfunction "RESET_6") (pintype "input"))
    )
    (net (code "67") (name "Net-(Q1-Gate)") (class "Default")
      (node (ref "Q1") (pin "1") (pinfunction "Gate_1") (pintype "passive"))
      (node (ref "R4") (pin "2") (pinfunction "2_2") (pintype "passive"))
      (node (ref "R5") (pin "2") (pinfunction "2_2") (pintype "passive"))
    )
    (net (code "68") (name "Net-(U1-BOOT0)") (class "Default")
      (node (ref "R2") (pin "2") (pinfunction "2_2") (pintype "passive"))
      (node (ref "U1") (pin "60") (pinfunction "BOOT0_60") (pintype "input"))
    )
    (net (code "69") (name "Net-(U1-PC14-OSC32_IN)") (class "Default")
      (node (ref "C7") (pin "1") (pinfunction "1_1") (pintype "passive"))
      (node (ref "U1") (pin "3") (pinfunction "PC14-OSC32_IN_3") (pintype "bidirectional"))
      (node (ref "X1") (pin "1") (pinfunction "X1_1") (pintype "passive"))
    )
    (net (code "70") (name "Net-(U1-PC15-OSC32_OUT)") (class "Default")
      (node (ref "C8") (pin "2") (pinfunction "2_2") (pintype "passive"))
      (node (ref "U1") (pin "4") (pinfunction "PC15-OSC32_OUT_4") (pintype "bidirectional"))
      (node (ref "X1") (pin "4") (pinfunction "X2_4") (pintype "passive"))
    )
    (net (code "71") (name "Net-(U1-VCAP1)") (class "Default")
      (node (ref "C4") (pin "2") (pinfunction "2_2") (pintype "passive"))
      (node (ref "U1") (pin "30") (pinfunction "VCAP1_30") (pintype "power_in"))
    )
    (net (code "72") (name "Net-(U3-FILTER)") (class "Default")
      (node (ref "C14") (pin "2") (pinfunction "2_2") (pintype "passive"))
      (node (ref "U3") (pin "6") (pinfunction "FILTER_6") (pintype "passive"))
    )
    (net (code "73") (name "unconnected-(MD1-LNA_EN-Pad14)") (class "Default")
      (node (ref "MD1") (pin "14") (pinfunction "LNA_EN_14") (pintype "output"))
    )
    (net (code "74") (name "unconnected-(MD1-Reserved-Pad15)") (class "Default")
      (node (ref "MD1") (pin "15") (pinfunction "Reserved_15") (pintype "passive"))
    )
    (net (code "75") (name "unconnected-(MD1-Reserved-Pad16)") (class "Default")
      (node (ref "MD1") (pin "16") (pinfunction "Reserved_16") (pintype "passive"))
    )
    (net (code "76") (name "unconnected-(MD1-Reserved-Pad17)") (class "Default")
      (node (ref "MD1") (pin "17") (pinfunction "Reserved_17") (pintype "passive"))
    )
    (net (code "77") (name "unconnected-(MD1-SCL{slash}SPI_SLK-Pad19)") (class "Default")
      (node (ref "MD1") (pin "19") (pinfunction "SCL/SPI_SLK_19") (pintype "bidirectional"))
    )
    (net (code "78") (name "unconnected-(MD1-SDA{slash}~{SPI_CS}-Pad18)") (class "Default")
      (node (ref "MD1") (pin "18") (pinfunction "SDA/~{SPI_CS}_18") (pintype "bidirectional"))
    )
    (net (code "79") (name "unconnected-(MD1-USB_DM-Pad5)") (class "Default")
      (node (ref "MD1") (pin "5") (pinfunction "USB_DM_5") (pintype "bidirectional"))
    )
    (net (code "80") (name "unconnected-(MD1-USB_DP-Pad6)") (class "Default")
      (node (ref "MD1") (pin "6") (pinfunction "USB_DP_6") (pintype "bidirectional"))
    )
    (net (code "81") (name "unconnected-(MD1-V_BCKP-Pad22)") (class "Default")
      (node (ref "MD1") (pin "22") (pinfunction "V_BCKP_22") (pintype "power_in"))
    )
    (net (code "82") (name "unconnected-(MD1-~{SAFEBOOT}-Pad1)") (class "Default")
      (node (ref "MD1") (pin "1") (pinfunction "~{SAFEBOOT}_1") (pintype "input"))
    )
    (net (code "83") (name "unconnected-(MD2-DIO0-Pad14)") (class "Default")
      (node (ref "MD2") (pin "14") (pinfunction "DIO0_14") (pintype "bidirectional"))
    )
    (net (code "84") (name "unconnected-(MD2-DIO1-Pad15)") (class "Default")
      (node (ref "MD2") (pin "15") (pinfunction "DIO1_15") (pintype "output"))
    )
    (net (code "85") (name "unconnected-(MD2-DIO2-Pad16)") (class "Default")
      (node (ref "MD2") (pin "16") (pinfunction "DIO2_16") (pintype "bidirectional"))
    )
    (net (code "86") (name "unconnected-(MD2-DIO3-Pad11)") (class "Default")
      (node (ref "MD2") (pin "11") (pinfunction "DIO3_11") (pintype "bidirectional"))
    )
    (net (code "87") (name "unconnected-(MD2-DIO4-Pad12)") (class "Default")
      (node (ref "MD2") (pin "12") (pinfunction "DIO4_12") (pintype "bidirectional"))
    )
    (net (code "88") (name "unconnected-(MD2-DIO5-Pad7)") (class "Default")
      (node (ref "MD2") (pin "7") (pinfunction "DIO5_7") (pintype "bidirectional"))
    )
    (net (code "89") (name "unconnected-(U1-PA11-Pad44)") (class "Default")
      (node (ref "U1") (pin "44") (pinfunction "PA11_44") (pintype "bidirectional"))
    )
    (net (code "90") (name "unconnected-(U1-PA12-Pad45)") (class "Default")
      (node (ref "U1") (pin "45") (pinfunction "PA12_45") (pintype "bidirectional"))
    )
    (net (code "91") (name "unconnected-(U1-PB4-Pad56)") (class "Default")
      (node (ref "U1") (pin "56") (pinfunction "PB4_56") (pintype "bidirectional"))
    )
    (net (code "92") (name "unconnected-(U1-PB5-Pad57)") (class "Default")
      (node (ref "U1") (pin "57") (pinfunction "PB5_57") (pintype "bidirectional"))
    )
    (net (code "93") (name "unconnected-(U1-PB6-Pad58)") (class "Default")
      (node (ref "U1") (pin "58") (pinfunction "PB6_58") (pintype "bidirectional"))
    )
    (net (code "94") (name "unconnected-(U1-PB7-Pad59)") (class "Default")
      (node (ref "U1") (pin "59") (pinfunction "PB7_59") (pintype "bidirectional"))
    )
    (net (code "95") (name "unconnected-(U1-PB12-Pad33)") (class "Default")
      (node (ref "U1") (pin "33") (pinfunction "PB12_33") (pintype "bidirectional"))
    )
    (net (code "96") (name "unconnected-(U1-PB14-Pad35)") (class "Default")
      (node (ref "U1") (pin "35") (pinfunction "PB14_35") (pintype "bidirectional"))
    )
    (net (code "97") (name "unconnected-(U1-PB15-Pad36)") (class "Default")
      (node (ref "U1") (pin "36") (pinfunction "PB15_36") (pintype "bidirectional"))
    )
    (net (code "98") (name "unconnected-(U1-PC3-Pad11)") (class "Default")
      (node (ref "U1") (pin "11") (pinfunction "PC3_11") (pintype "bidirectional"))
    )
    (net (code "99") (name "unconnected-(U1-PC8-Pad39)") (class "Default")
      (node (ref "U1") (pin "39") (pinfunction "PC8_39") (pintype "bidirectional"))
    )
    (net (code "100") (name "unconnected-(U1-PC13-Pad2)") (class "Default")
      (node (ref "U1") (pin "2") (pinfunction "PC13_2") (pintype "bidirectional"))
    )
    (net (code "101") (name "unconnected-(U1-PH0-OSC_IN-Pad5)") (class "Default")
      (node (ref "U1") (pin "5") (pinfunction "PH0-OSC_IN_5") (pintype "bidirectional"))
    )
    (net (code "102") (name "unconnected-(U1-PH1-OSC_OUT-Pad6)") (class "Default")
      (node (ref "U1") (pin "6") (pinfunction "PH1-OSC_OUT_6") (pintype "bidirectional"))
    )
    (net (code "103") (name "unconnected-(U4-VOUT-Pad4)") (class "Default")
      (node (ref "U4") (pin "4") (pinfunction "VOUT_4") (pintype "power_in"))
    )
    (net (code "104") (name "unconnected-(X1-NC-Pad2)") (class "Default")
      (node (ref "X1") (pin "2") (pinfunction "NC_2") (pintype "passive"))
    )
    (net (code "105") (name "unconnected-(X1-NC-Pad3)") (class "Default")
      (node (ref "X1") (pin "3") (pinfunction "NC_3") (pintype "passive"))
    )
  )
)
